# overear_schematic_original_format.net
KiCad netlist of a schematic drawn in EasyEDA
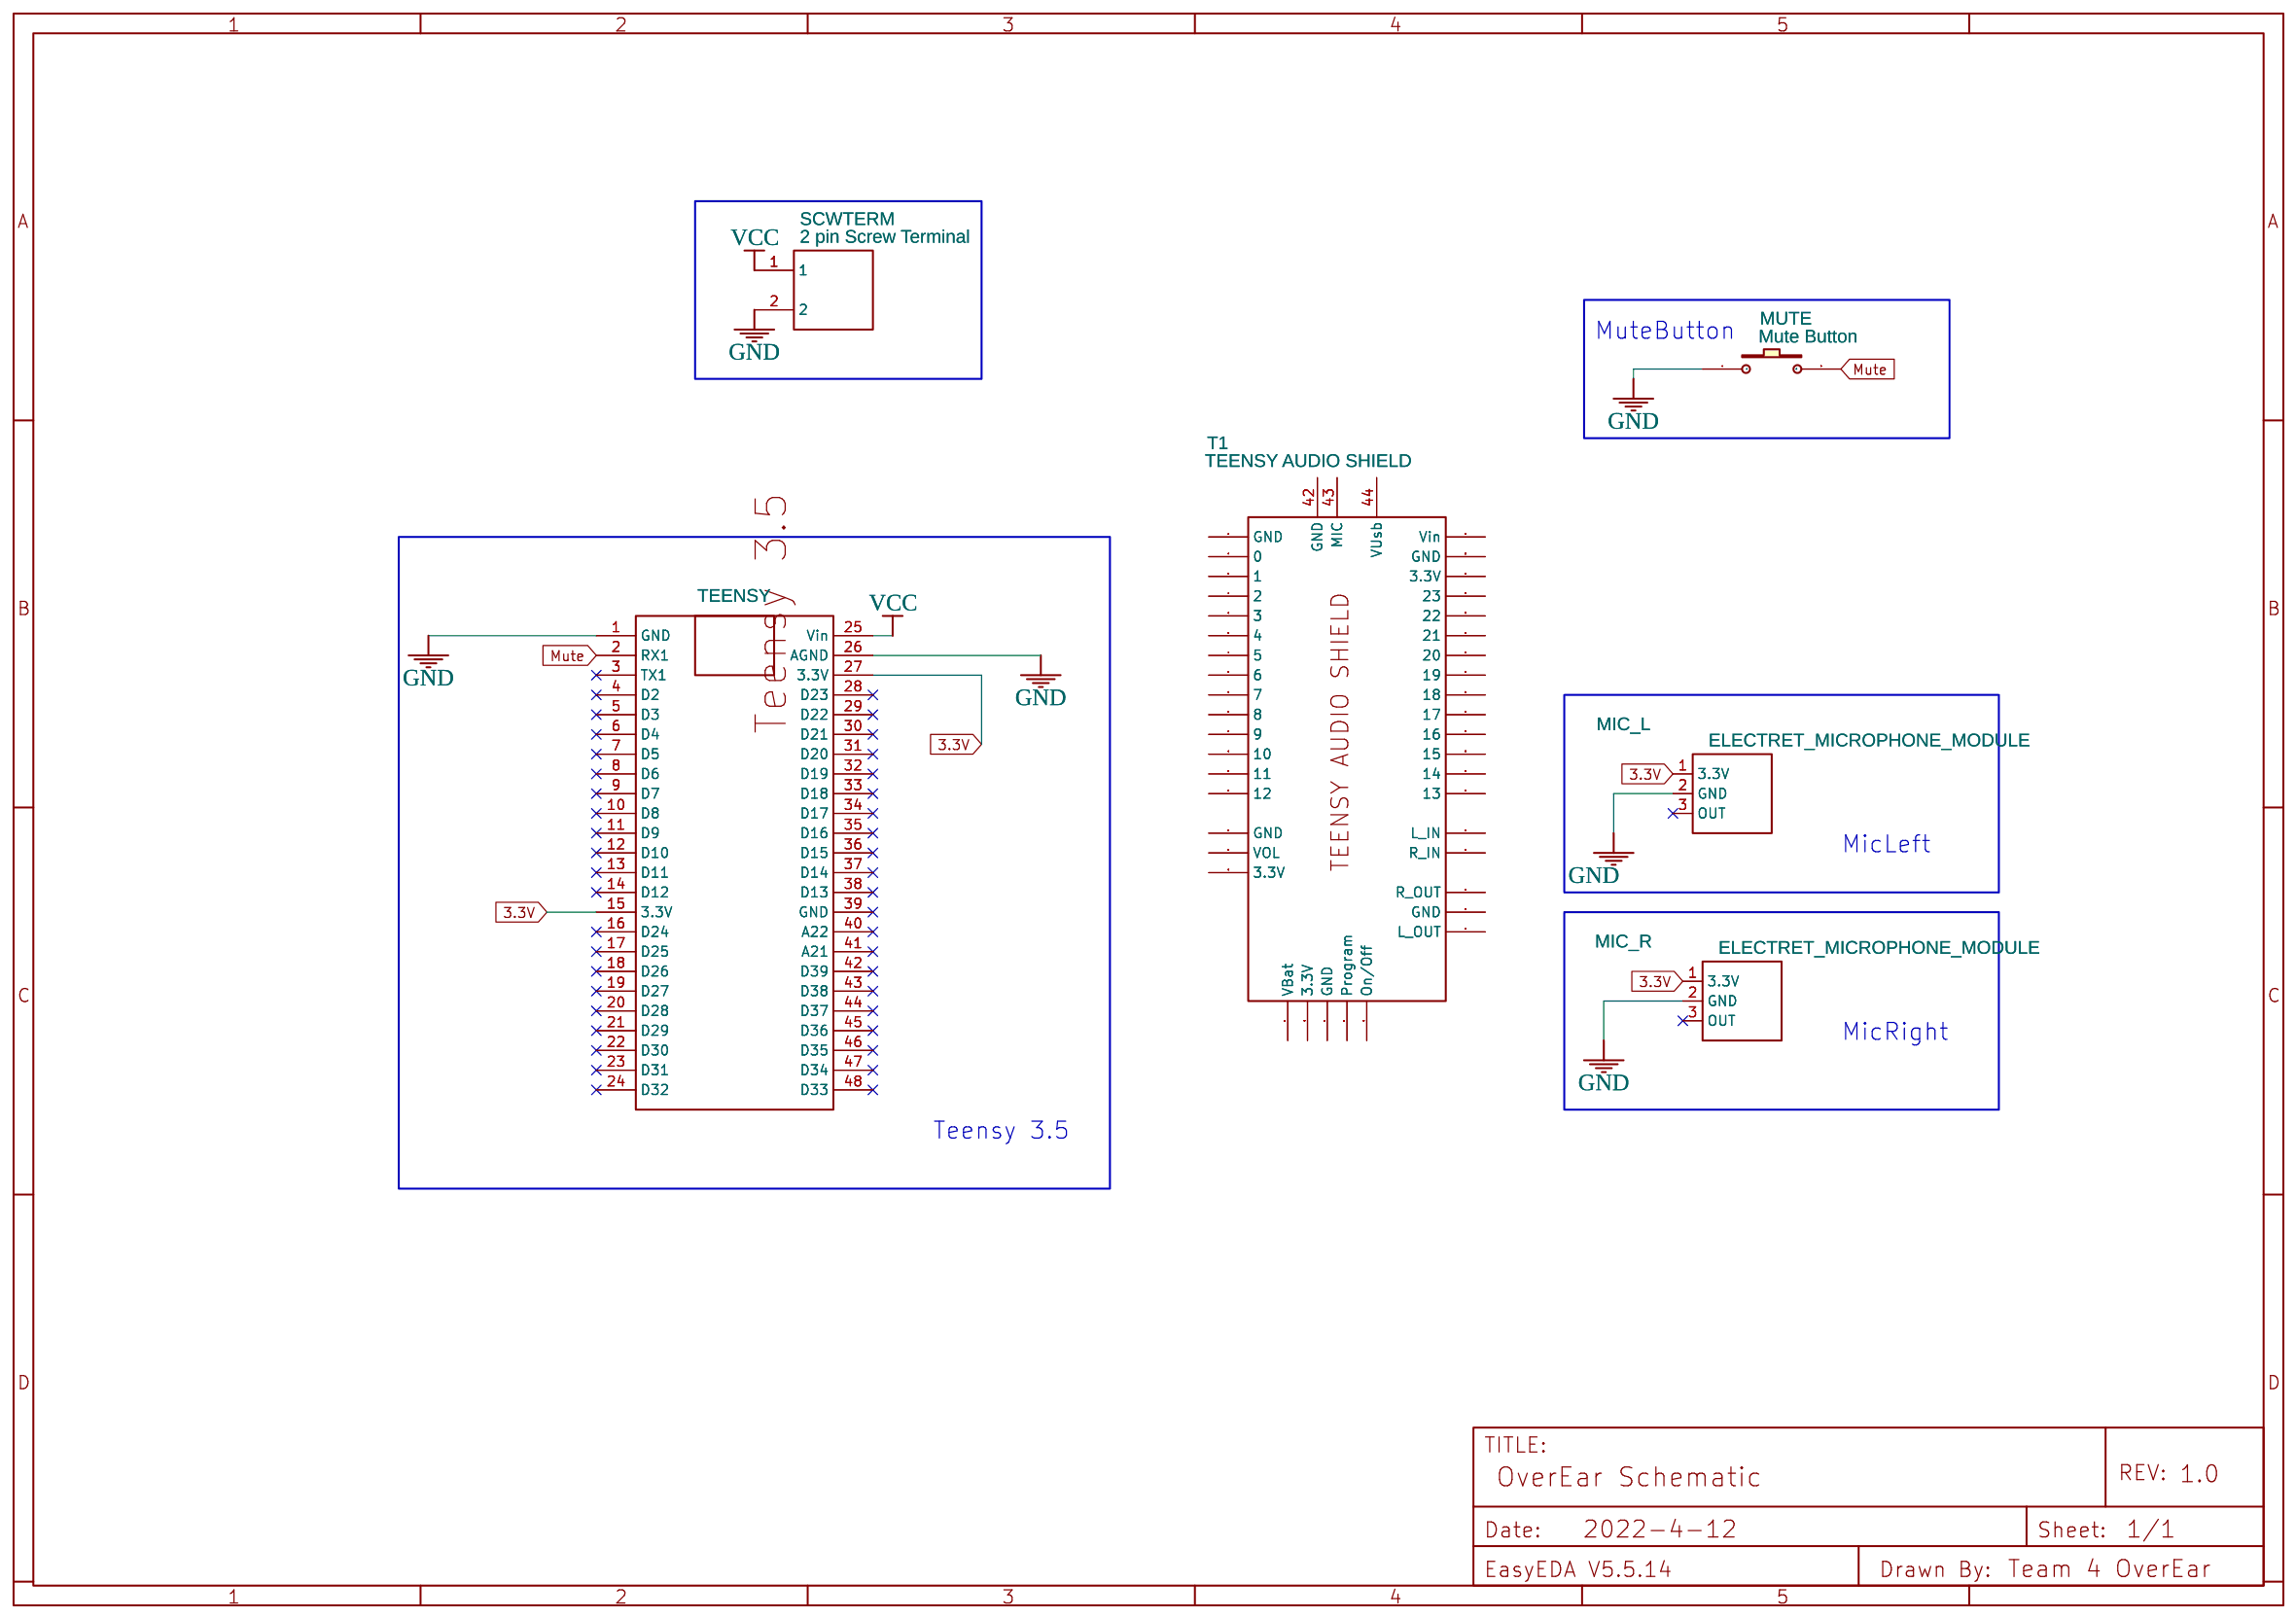
[diagram p0: schematic sheet]

(export (version "E")
  (design (tool "Eeschema 10.0.6"))
  (components
    (comp (ref "MIC_L")
      (value "ELECTRET_MICROPHONE_MODULE")
      (libsource (lib "") (part "ELECTRET_MICROPHONE_MODULE_1"))
    )
    (comp (ref "MIC_R")
      (value "ELECTRET_MICROPHONE_MODULE")
      (libsource (lib "") (part "ELECTRET_MICROPHONE_MODULE"))
    )
    (comp (ref "MUTE") (value "Mute Button") (libsource (lib "") (part "Button1")))
    (comp (ref "SCWTERM") (value "2 pin Screw Terminal") (libsource (lib "") (part "2 pin Screw Terminal")))
    (comp (ref "T1")
      (value "TEENSY AUDIO SHIELD")
      (fields (field (name "BOM_Manufacturer Part") "PJRC"))
      (libsource (lib "") (part "TEENSY AUDIO SHIELD"))
    )
    (comp (ref "TEENSY") (value "Teensy 3.5") (libsource (lib "") (part "Unknown_365_420")))
  )
  (nets
    (net (code "1") (name "3.3V") (class "Default")
      (node (ref "MIC_L") (pin "1") (pinfunction "3.3V_1") (pintype "unspecified"))
      (node (ref "MIC_R") (pin "1") (pinfunction "3.3V_1") (pintype "unspecified"))
      (node (ref "TEENSY") (pin "15") (pinfunction "3.3V_15") (pintype "unspecified"))
      (node (ref "TEENSY") (pin "27") (pinfunction "3.3V_27") (pintype "unspecified"))
    )
    (net (code "2") (name "GND") (class "Default")
      (node (ref "MIC_L") (pin "2") (pinfunction "GND_2") (pintype "unspecified"))
      (node (ref "MIC_R") (pin "2") (pinfunction "GND_2") (pintype "unspecified"))
      (node (ref "MUTE") (pin "1") (pinfunction "1_1") (pintype "bidirectional"))
      (node (ref "SCWTERM") (pin "2") (pinfunction "2_2") (pintype "unspecified"))
      (node (ref "TEENSY") (pin "1") (pinfunction "GND_1") (pintype "unspecified"))
      (node (ref "TEENSY") (pin "26") (pinfunction "AGND_26") (pintype "unspecified"))
    )
    (net (code "3") (name "Mute") (class "Default")
      (node (ref "MUTE") (pin "2") (pinfunction "2_2") (pintype "bidirectional"))
      (node (ref "TEENSY") (pin "2") (pinfunction "RX1_2") (pintype "unspecified"))
    )
    (net (code "4") (name "VCC") (class "Default")
      (node (ref "SCWTERM") (pin "1") (pinfunction "1_1") (pintype "unspecified"))
      (node (ref "TEENSY") (pin "25") (pinfunction "Vin_25") (pintype "unspecified"))
    )
    (net (code "5") (name "unconnected-(MIC_L-OUT-Pad3)") (class "Default")
      (node (ref "MIC_L") (pin "3") (pinfunction "OUT_3") (pintype "unspecified+no_connect"))
    )
    (net (code "6") (name "unconnected-(MIC_R-OUT-Pad3)") (class "Default")
      (node (ref "MIC_R") (pin "3") (pinfunction "OUT_3") (pintype "unspecified+no_connect"))
    )
    (net (code "7") (name "unconnected-(T1-0-Pad2)") (class "Default")
      (node (ref "T1") (pin "2") (pinfunction "0_2") (pintype "unspecified"))
    )
    (net (code "8") (name "unconnected-(T1-1-Pad3)") (class "Default")
      (node (ref "T1") (pin "3") (pinfunction "1_3") (pintype "unspecified"))
    )
    (net (code "9") (name "unconnected-(T1-2-Pad4)") (class "Default")
      (node (ref "T1") (pin "4") (pinfunction "2_4") (pintype "unspecified"))
    )
    (net (code "10") (name "unconnected-(T1-3-Pad5)") (class "Default")
      (node (ref "T1") (pin "5") (pinfunction "3_5") (pintype "unspecified"))
    )
    (net (code "11") (name "unconnected-(T1-3.3V-Pad16)") (class "Default")
      (node (ref "T1") (pin "16") (pinfunction "3.3V_16") (pintype "unspecified"))
    )
    (net (code "12") (name "unconnected-(T1-3.3V-Pad31)") (class "Default")
      (node (ref "T1") (pin "31") (pinfunction "3.3V_31") (pintype "unspecified"))
    )
    (net (code "13") (name "unconnected-(T1-3.3V-Pad34)") (class "Default")
      (node (ref "T1") (pin "34") (pinfunction "3.3V_34") (pintype "unspecified"))
    )
    (net (code "14") (name "unconnected-(T1-4-Pad6)") (class "Default")
      (node (ref "T1") (pin "6") (pinfunction "4_6") (pintype "unspecified"))
    )
    (net (code "15") (name "unconnected-(T1-5-Pad7)") (class "Default")
      (node (ref "T1") (pin "7") (pinfunction "5_7") (pintype "unspecified"))
    )
    (net (code "16") (name "unconnected-(T1-6-Pad8)") (class "Default")
      (node (ref "T1") (pin "8") (pinfunction "6_8") (pintype "unspecified"))
    )
    (net (code "17") (name "unconnected-(T1-7-Pad9)") (class "Default")
      (node (ref "T1") (pin "9") (pinfunction "7_9") (pintype "unspecified"))
    )
    (net (code "18") (name "unconnected-(T1-8-Pad10)") (class "Default")
      (node (ref "T1") (pin "10") (pinfunction "8_10") (pintype "unspecified"))
    )
    (net (code "19") (name "unconnected-(T1-9-Pad11)") (class "Default")
      (node (ref "T1") (pin "11") (pinfunction "9_11") (pintype "unspecified"))
    )
    (net (code "20") (name "unconnected-(T1-10-Pad12)") (class "Default")
      (node (ref "T1") (pin "12") (pinfunction "10_12") (pintype "unspecified"))
    )
    (net (code "21") (name "unconnected-(T1-11-Pad13)") (class "Default")
      (node (ref "T1") (pin "13") (pinfunction "11_13") (pintype "unspecified"))
    )
    (net (code "22") (name "unconnected-(T1-12-Pad14)") (class "Default")
      (node (ref "T1") (pin "14") (pinfunction "12_14") (pintype "unspecified"))
    )
    (net (code "23") (name "unconnected-(T1-13-Pad20)") (class "Default")
      (node (ref "T1") (pin "20") (pinfunction "13_20") (pintype "unspecified"))
    )
    (net (code "24") (name "unconnected-(T1-14-Pad21)") (class "Default")
      (node (ref "T1") (pin "21") (pinfunction "14_21") (pintype "unspecified"))
    )
    (net (code "25") (name "unconnected-(T1-15-Pad22)") (class "Default")
      (node (ref "T1") (pin "22") (pinfunction "15_22") (pintype "unspecified"))
    )
    (net (code "26") (name "unconnected-(T1-16-Pad23)") (class "Default")
      (node (ref "T1") (pin "23") (pinfunction "16_23") (pintype "unspecified"))
    )
    (net (code "27") (name "unconnected-(T1-17-Pad24)") (class "Default")
      (node (ref "T1") (pin "24") (pinfunction "17_24") (pintype "unspecified"))
    )
    (net (code "28") (name "unconnected-(T1-18-Pad25)") (class "Default")
      (node (ref "T1") (pin "25") (pinfunction "18_25") (pintype "unspecified"))
    )
    (net (code "29") (name "unconnected-(T1-19-Pad26)") (class "Default")
      (node (ref "T1") (pin "26") (pinfunction "19_26") (pintype "unspecified"))
    )
    (net (code "30") (name "unconnected-(T1-20-Pad27)") (class "Default")
      (node (ref "T1") (pin "27") (pinfunction "20_27") (pintype "unspecified"))
    )
    (net (code "31") (name "unconnected-(T1-21-Pad28)") (class "Default")
      (node (ref "T1") (pin "28") (pinfunction "21_28") (pintype "unspecified"))
    )
    (net (code "32") (name "unconnected-(T1-22-Pad29)") (class "Default")
      (node (ref "T1") (pin "29") (pinfunction "22_29") (pintype "unspecified"))
    )
    (net (code "33") (name "unconnected-(T1-23-Pad30)") (class "Default")
      (node (ref "T1") (pin "30") (pinfunction "23_30") (pintype "unspecified"))
    )
    (net (code "34") (name "unconnected-(T1-GND-Pad1)") (class "Default")
      (node (ref "T1") (pin "1") (pinfunction "GND_1") (pintype "unspecified"))
    )
    (net (code "35") (name "unconnected-(T1-GND-Pad17)") (class "Default")
      (node (ref "T1") (pin "17") (pinfunction "GND_17") (pintype "unspecified"))
    )
    (net (code "36") (name "unconnected-(T1-GND-Pad32)") (class "Default")
      (node (ref "T1") (pin "32") (pinfunction "GND_32") (pintype "unspecified"))
    )
    (net (code "37") (name "unconnected-(T1-GND-Pad36)") (class "Default")
      (node (ref "T1") (pin "36") (pinfunction "GND_36") (pintype "unspecified"))
    )
    (net (code "38") (name "unconnected-(T1-GND-Pad40)") (class "Default")
      (node (ref "T1") (pin "40") (pinfunction "GND_40") (pintype "unspecified"))
    )
    (net (code "39") (name "unconnected-(T1-GND-Pad42)") (class "Default")
      (node (ref "T1") (pin "42") (pinfunction "GND_42") (pintype "unspecified"))
    )
    (net (code "40") (name "unconnected-(T1-L_IN-Pad37)") (class "Default")
      (node (ref "T1") (pin "37") (pinfunction "L_IN_37") (pintype "unspecified"))
    )
    (net (code "41") (name "unconnected-(T1-L_OUT-Pad41)") (class "Default")
      (node (ref "T1") (pin "41") (pinfunction "L_OUT_41") (pintype "unspecified"))
    )
    (net (code "42") (name "unconnected-(T1-MIC-Pad43)") (class "Default")
      (node (ref "T1") (pin "43") (pinfunction "MIC_43") (pintype "unspecified"))
    )
    (net (code "43") (name "unconnected-(T1-On{slash}Off-Pad19)") (class "Default")
      (node (ref "T1") (pin "19") (pinfunction "On/Off_19") (pintype "unspecified"))
    )
    (net (code "44") (name "unconnected-(T1-Program-Pad18)") (class "Default")
      (node (ref "T1") (pin "18") (pinfunction "Program_18") (pintype "unspecified"))
    )
    (net (code "45") (name "unconnected-(T1-R_IN-Pad38)") (class "Default")
      (node (ref "T1") (pin "38") (pinfunction "R_IN_38") (pintype "unspecified"))
    )
    (net (code "46") (name "unconnected-(T1-R_OUT-Pad39)") (class "Default")
      (node (ref "T1") (pin "39") (pinfunction "R_OUT_39") (pintype "unspecified"))
    )
    (net (code "47") (name "unconnected-(T1-VBat-Pad15)") (class "Default")
      (node (ref "T1") (pin "15") (pinfunction "VBat_15") (pintype "unspecified"))
    )
    (net (code "48") (name "unconnected-(T1-VOL-Pad35)") (class "Default")
      (node (ref "T1") (pin "35") (pinfunction "VOL_35") (pintype "unspecified"))
    )
    (net (code "49") (name "unconnected-(T1-VUsb-Pad44)") (class "Default")
      (node (ref "T1") (pin "44") (pinfunction "VUsb_44") (pintype "unspecified"))
    )
    (net (code "50") (name "unconnected-(T1-Vin-Pad33)") (class "Default")
      (node (ref "T1") (pin "33") (pinfunction "Vin_33") (pintype "unspecified"))
    )
    (net (code "51") (name "unconnected-(TEENSY-A21-Pad41)") (class "Default")
      (node (ref "TEENSY") (pin "41") (pinfunction "A21_41") (pintype "unspecified+no_connect"))
    )
    (net (code "52") (name "unconnected-(TEENSY-A22-Pad40)") (class "Default")
      (node (ref "TEENSY") (pin "40") (pinfunction "A22_40") (pintype "unspecified+no_connect"))
    )
    (net (code "53") (name "unconnected-(TEENSY-D2-Pad4)") (class "Default")
      (node (ref "TEENSY") (pin "4") (pinfunction "D2_4") (pintype "unspecified+no_connect"))
    )
    (net (code "54") (name "unconnected-(TEENSY-D3-Pad5)") (class "Default")
      (node (ref "TEENSY") (pin "5") (pinfunction "D3_5") (pintype "unspecified+no_connect"))
    )
    (net (code "55") (name "unconnected-(TEENSY-D4-Pad6)") (class "Default")
      (node (ref "TEENSY") (pin "6") (pinfunction "D4_6") (pintype "unspecified+no_connect"))
    )
    (net (code "56") (name "unconnected-(TEENSY-D5-Pad7)") (class "Default")
      (node (ref "TEENSY") (pin "7") (pinfunction "D5_7") (pintype "unspecified+no_connect"))
    )
    (net (code "57") (name "unconnected-(TEENSY-D6-Pad8)") (class "Default")
      (node (ref "TEENSY") (pin "8") (pinfunction "D6_8") (pintype "unspecified+no_connect"))
    )
    (net (code "58") (name "unconnected-(TEENSY-D7-Pad9)") (class "Default")
      (node (ref "TEENSY") (pin "9") (pinfunction "D7_9") (pintype "unspecified+no_connect"))
    )
    (net (code "59") (name "unconnected-(TEENSY-D8-Pad10)") (class "Default")
      (node (ref "TEENSY") (pin "10") (pinfunction "D8_10") (pintype "unspecified+no_connect"))
    )
    (net (code "60") (name "unconnected-(TEENSY-D9-Pad11)") (class "Default")
      (node (ref "TEENSY") (pin "11") (pinfunction "D9_11") (pintype "unspecified+no_connect"))
    )
    (net (code "61") (name "unconnected-(TEENSY-D10-Pad12)") (class "Default")
      (node (ref "TEENSY") (pin "12") (pinfunction "D10_12") (pintype "unspecified+no_connect"))
    )
    (net (code "62") (name "unconnected-(TEENSY-D11-Pad13)") (class "Default")
      (node (ref "TEENSY") (pin "13") (pinfunction "D11_13") (pintype "unspecified+no_connect"))
    )
    (net (code "63") (name "unconnected-(TEENSY-D12-Pad14)") (class "Default")
      (node (ref "TEENSY") (pin "14") (pinfunction "D12_14") (pintype "unspecified+no_connect"))
    )
    (net (code "64") (name "unconnected-(TEENSY-D13-Pad38)") (class "Default")
      (node (ref "TEENSY") (pin "38") (pinfunction "D13_38") (pintype "unspecified+no_connect"))
    )
    (net (code "65") (name "unconnected-(TEENSY-D14-Pad37)") (class "Default")
      (node (ref "TEENSY") (pin "37") (pinfunction "D14_37") (pintype "unspecified+no_connect"))
    )
    (net (code "66") (name "unconnected-(TEENSY-D15-Pad36)") (class "Default")
      (node (ref "TEENSY") (pin "36") (pinfunction "D15_36") (pintype "unspecified+no_connect"))
    )
    (net (code "67") (name "unconnected-(TEENSY-D16-Pad35)") (class "Default")
      (node (ref "TEENSY") (pin "35") (pinfunction "D16_35") (pintype "unspecified+no_connect"))
    )
    (net (code "68") (name "unconnected-(TEENSY-D17-Pad34)") (class "Default")
      (node (ref "TEENSY") (pin "34") (pinfunction "D17_34") (pintype "unspecified+no_connect"))
    )
    (net (code "69") (name "unconnected-(TEENSY-D18-Pad33)") (class "Default")
      (node (ref "TEENSY") (pin "33") (pinfunction "D18_33") (pintype "unspecified+no_connect"))
    )
    (net (code "70") (name "unconnected-(TEENSY-D19-Pad32)") (class "Default")
      (node (ref "TEENSY") (pin "32") (pinfunction "D19_32") (pintype "unspecified+no_connect"))
    )
    (net (code "71") (name "unconnected-(TEENSY-D20-Pad31)") (class "Default")
      (node (ref "TEENSY") (pin "31") (pinfunction "D20_31") (pintype "unspecified+no_connect"))
    )
    (net (code "72") (name "unconnected-(TEENSY-D21-Pad30)") (class "Default")
      (node (ref "TEENSY") (pin "30") (pinfunction "D21_30") (pintype "unspecified+no_connect"))
    )
    (net (code "73") (name "unconnected-(TEENSY-D22-Pad29)") (class "Default")
      (node (ref "TEENSY") (pin "29") (pinfunction "D22_29") (pintype "unspecified+no_connect"))
    )
    (net (code "74") (name "unconnected-(TEENSY-D23-Pad28)") (class "Default")
      (node (ref "TEENSY") (pin "28") (pinfunction "D23_28") (pintype "unspecified+no_connect"))
    )
    (net (code "75") (name "unconnected-(TEENSY-D24-Pad16)") (class "Default")
      (node (ref "TEENSY") (pin "16") (pinfunction "D24_16") (pintype "unspecified+no_connect"))
    )
    (net (code "76") (name "unconnected-(TEENSY-D25-Pad17)") (class "Default")
      (node (ref "TEENSY") (pin "17") (pinfunction "D25_17") (pintype "unspecified+no_connect"))
    )
    (net (code "77") (name "unconnected-(TEENSY-D26-Pad18)") (class "Default")
      (node (ref "TEENSY") (pin "18") (pinfunction "D26_18") (pintype "unspecified+no_connect"))
    )
    (net (code "78") (name "unconnected-(TEENSY-D27-Pad19)") (class "Default")
      (node (ref "TEENSY") (pin "19") (pinfunction "D27_19") (pintype "unspecified+no_connect"))
    )
    (net (code "79") (name "unconnected-(TEENSY-D28-Pad20)") (class "Default")
      (node (ref "TEENSY") (pin "20") (pinfunction "D28_20") (pintype "unspecified+no_connect"))
    )
    (net (code "80") (name "unconnected-(TEENSY-D29-Pad21)") (class "Default")
      (node (ref "TEENSY") (pin "21") (pinfunction "D29_21") (pintype "unspecified+no_connect"))
    )
    (net (code "81") (name "unconnected-(TEENSY-D30-Pad22)") (class "Default")
      (node (ref "TEENSY") (pin "22") (pinfunction "D30_22") (pintype "unspecified+no_connect"))
    )
    (net (code "82") (name "unconnected-(TEENSY-D31-Pad23)") (class "Default")
      (node (ref "TEENSY") (pin "23") (pinfunction "D31_23") (pintype "unspecified+no_connect"))
    )
    (net (code "83") (name "unconnected-(TEENSY-D32-Pad24)") (class "Default")
      (node (ref "TEENSY") (pin "24") (pinfunction "D32_24") (pintype "unspecified+no_connect"))
    )
    (net (code "84") (name "unconnected-(TEENSY-D33-Pad48)") (class "Default")
      (node (ref "TEENSY") (pin "48") (pinfunction "D33_48") (pintype "unspecified+no_connect"))
    )
    (net (code "85") (name "unconnected-(TEENSY-D34-Pad47)") (class "Default")
      (node (ref "TEENSY") (pin "47") (pinfunction "D34_47") (pintype "unspecified+no_connect"))
    )
    (net (code "86") (name "unconnected-(TEENSY-D35-Pad46)") (class "Default")
      (node (ref "TEENSY") (pin "46") (pinfunction "D35_46") (pintype "unspecified+no_connect"))
    )
    (net (code "87") (name "unconnected-(TEENSY-D36-Pad45)") (class "Default")
      (node (ref "TEENSY") (pin "45") (pinfunction "D36_45") (pintype "unspecified+no_connect"))
    )
    (net (code "88") (name "unconnected-(TEENSY-D37-Pad44)") (class "Default")
      (node (ref "TEENSY") (pin "44") (pinfunction "D37_44") (pintype "unspecified+no_connect"))
    )
    (net (code "89") (name "unconnected-(TEENSY-D38-Pad43)") (class "Default")
      (node (ref "TEENSY") (pin "43") (pinfunction "D38_43") (pintype "unspecified+no_connect"))
    )
    (net (code "90") (name "unconnected-(TEENSY-D39-Pad42)") (class "Default")
      (node (ref "TEENSY") (pin "42") (pinfunction "D39_42") (pintype "unspecified+no_connect"))
    )
    (net (code "91") (name "unconnected-(TEENSY-GND-Pad39)") (class "Default")
      (node (ref "TEENSY") (pin "39") (pinfunction "GND_39") (pintype "unspecified+no_connect"))
    )
    (net (code "92") (name "unconnected-(TEENSY-TX1-Pad3)") (class "Default")
      (node (ref "TEENSY") (pin "3") (pinfunction "TX1_3") (pintype "unspecified+no_connect"))
    )
  )
)
